# pool_mesurement_circuit.net
KiCad netlist of a schematic drawn in Altium Designer
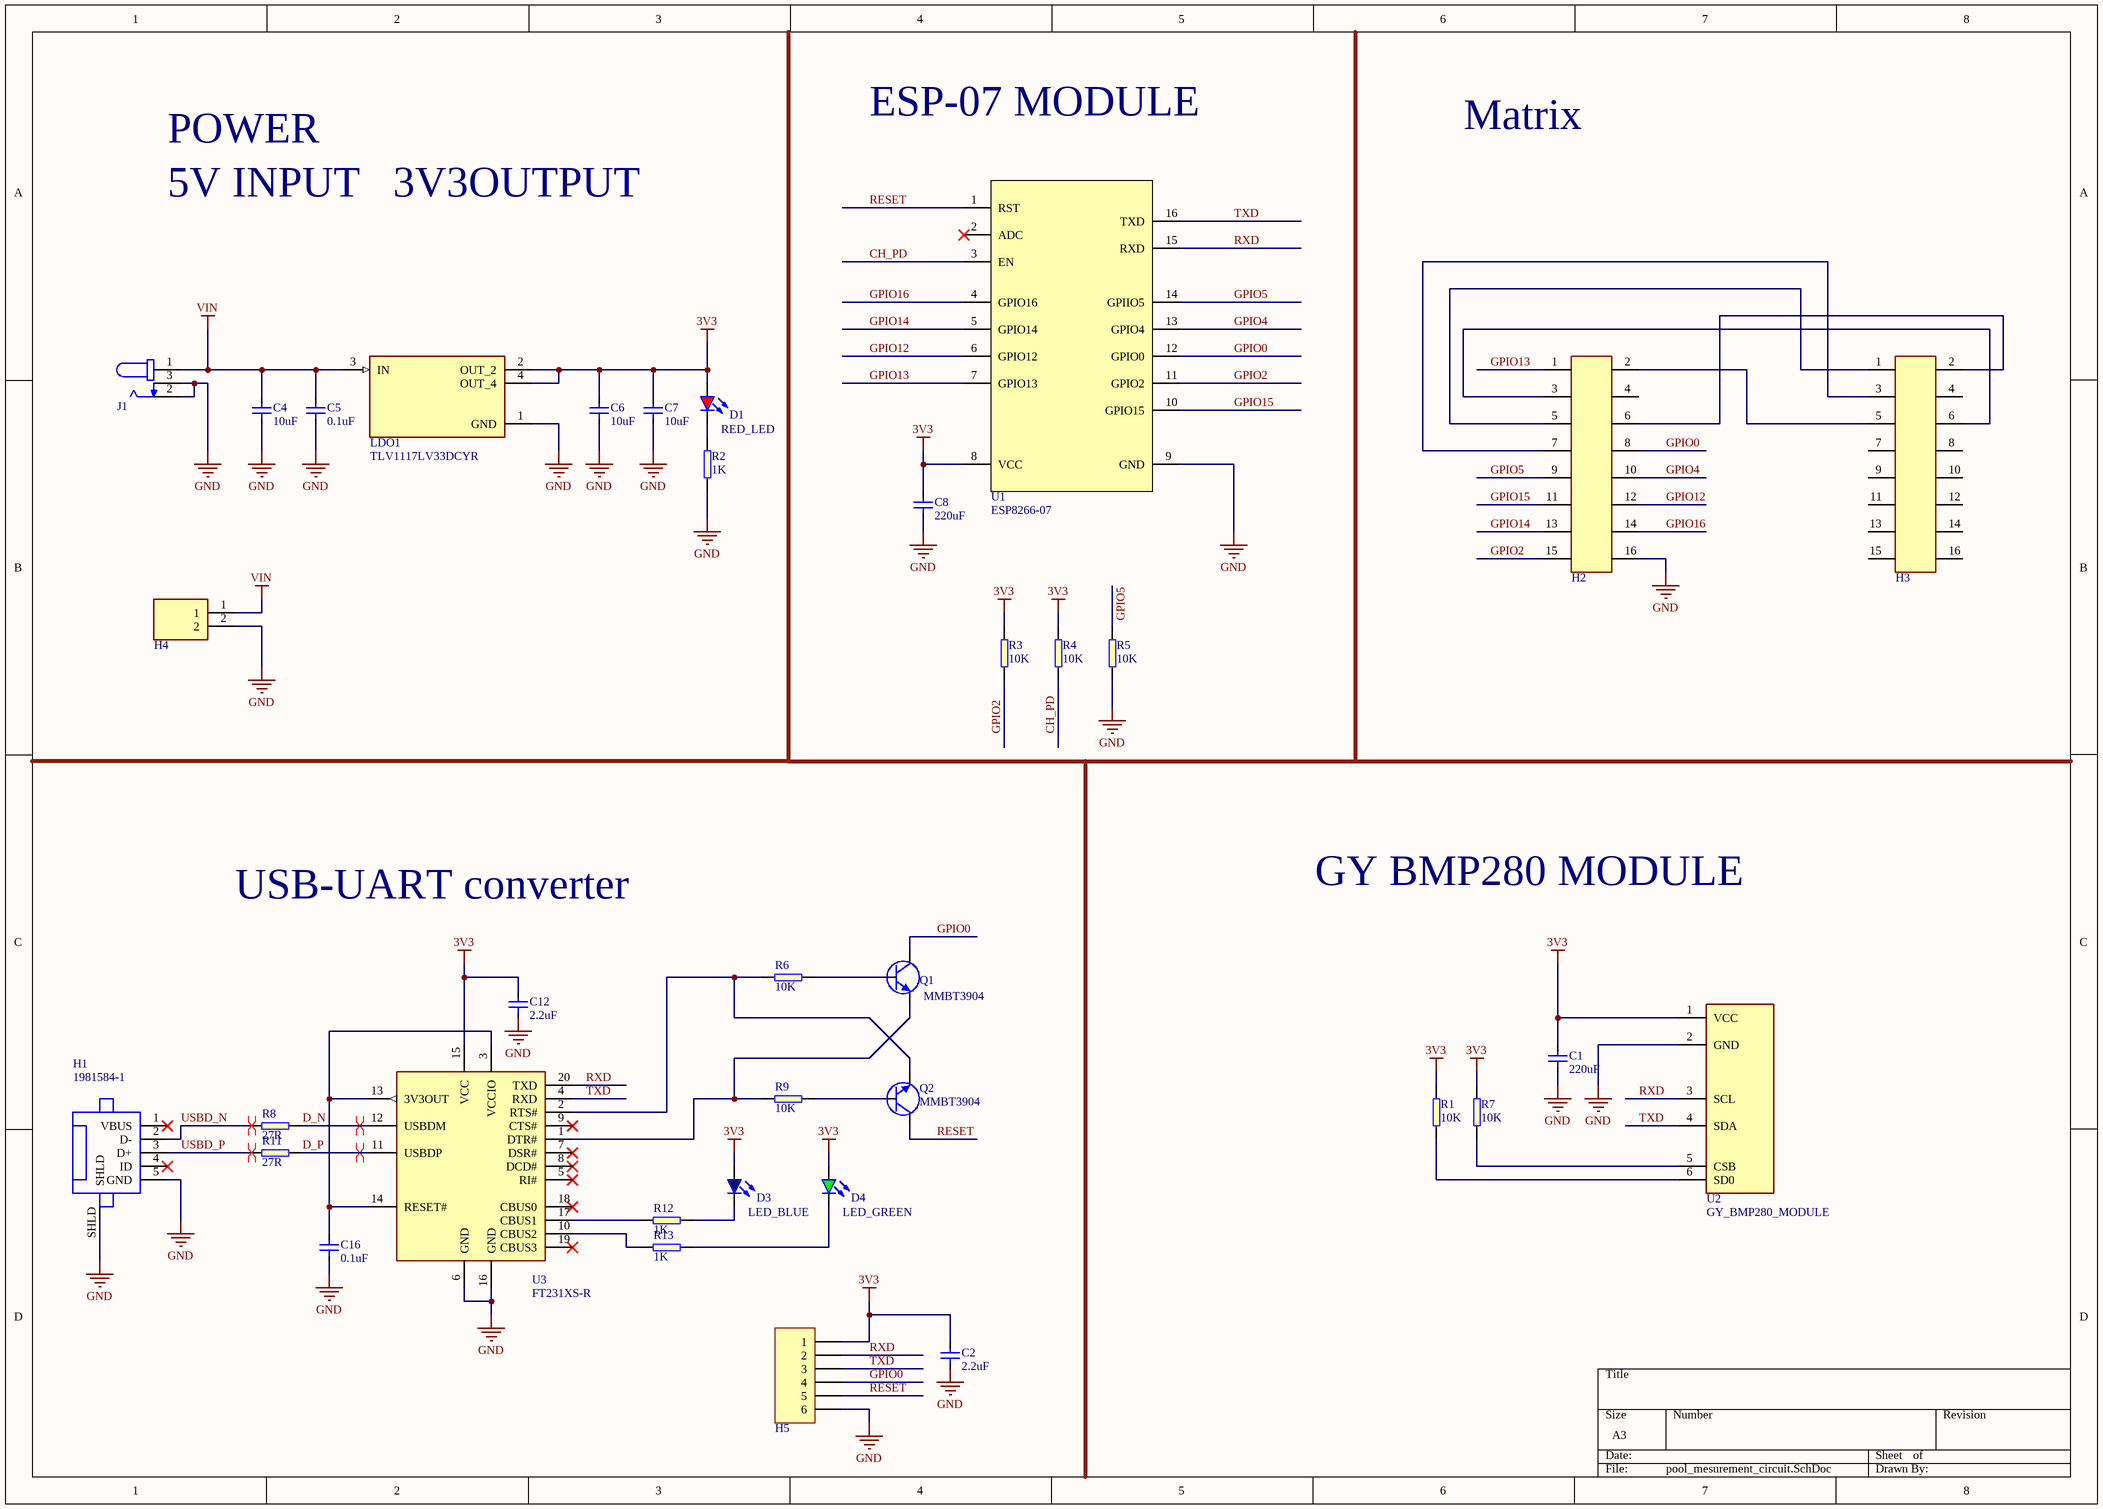
[diagram p0: pool_mesurement_circuit.SchDoc]

(export (version "E")
  (design (tool "Eeschema 10.0.6"))
  (components
    (comp (ref "C1")
      (value "220uF")
      (footprint "C3216")
      (description "SMD capacitor X6S(EIA) with capacitance 220uF Tol.20%. Rated voltage 4Vdc 105C")
      (fields (field (name "MANUFACTURER") "Murata Electronics"))
      (libsource (lib "SchLib") (part "C_220u_3216"))
    )
    (comp (ref "C2")
      (value "2.2uF")
      (footprint "C3216")
      (description "±10% 25V Ceramic Capacitor X7R 1206 (3216 Metric)")
      (fields (field (name "MANUFACTURER") "Samsung Electro-Mechanics"))
      (libsource (lib "SchLib") (part "C_2u2_3216"))
    )
    (comp (ref "C4")
      (value "10uF")
      (footprint "C3216")
      (description "-20%, +80% 10V Ceramic Capacitor Y5V (F) 1206 (3216 Metric)")
      (fields (field (name "MANUFACTURER") "Samsung Electro-Mechanics"))
      (libsource (lib "SchLib") (part "C_10u_3216"))
    )
    (comp (ref "C5")
      (value "0.1uF")
      (footprint "C3216")
      (description "±10% 50V Ceramic Capacitor X7R 1206 (3216 Metric)")
      (fields (field (name "MANUFACTURER") "Samsung Electro-Mechanics"))
      (libsource (lib "SchLib") (part "C_100n_3216"))
    )
    (comp (ref "C6")
      (value "10uF")
      (footprint "C3216")
      (description "-20%, +80% 10V Ceramic Capacitor Y5V (F) 1206 (3216 Metric)")
      (fields (field (name "MANUFACTURER") "Samsung Electro-Mechanics"))
      (libsource (lib "SchLib") (part "C_10u_3216"))
    )
    (comp (ref "C7")
      (value "10uF")
      (footprint "C3216")
      (description "-20%, +80% 10V Ceramic Capacitor Y5V (F) 1206 (3216 Metric)")
      (fields (field (name "MANUFACTURER") "Samsung Electro-Mechanics"))
      (libsource (lib "SchLib") (part "C_10u_3216"))
    )
    (comp (ref "C8")
      (value "220uF")
      (footprint "C3216")
      (description "SMD capacitor X6S(EIA) with capacitance 220uF Tol.20%. Rated voltage 4Vdc 105C")
      (fields (field (name "MANUFACTURER") "Murata Electronics"))
      (libsource (lib "SchLib") (part "C_220u_3216"))
    )
    (comp (ref "C12")
      (value "2.2uF")
      (footprint "C3216")
      (description "±10% 25V Ceramic Capacitor X7R 1206 (3216 Metric)")
      (fields (field (name "MANUFACTURER") "Samsung Electro-Mechanics"))
      (libsource (lib "SchLib") (part "C_2u2_3216"))
    )
    (comp (ref "C16")
      (value "0.1uF")
      (footprint "C3216")
      (description "±10% 50V Ceramic Capacitor X7R 1206 (3216 Metric)")
      (fields (field (name "MANUFACTURER") "Samsung Electro-Mechanics"))
      (libsource (lib "SchLib") (part "C_100n_3216"))
    )
    (comp (ref "D1")
      (value "RED_LED")
      (footprint "LED0603-RED")
      (description "Red 630nm LED Indication - Discrete 1.9V 0603 (1608 Metric)")
      (fields (field (name "MANUFACTURER") "Würth Elektronik"))
      (libsource (lib "SchLib") (part "LED_RED"))
    )
    (comp (ref "D3")
      (value "LED_BLUE")
      (footprint "LED0603-BLUE")
      (description "Blue 470nm LED Indication - Discrete 3.2V 0603 (1608 Metric)")
      (fields (field (name "MANUFACTURER") "Würth Elektronik"))
      (libsource (lib "SchLib") (part "LED_BLUE"))
    )
    (comp (ref "D4")
      (value "LED_GREEN")
      (footprint "LED0603-GRENN")
      (description "Green 520nm LED Indication - Discrete 3.2V 0603 (1608 Metric)")
      (fields (field (name "MANUFACTURER") "Würth Elektronik"))
      (libsource (lib "SchLib") (part "LED_GREEN"))
    )
    (comp (ref "H1")
      (value "1981584-1")
      (footprint "1981584-1")
      (description "Conn Micro USB 2.0 Type AB RCP 5 POS 0.65mm Solder RA SMD 5 Terminal 1 Port T/R")
      (fields (field (name "MANUFACTURER") "TE Connectivity"))
      (libsource (lib "SchLib") (part "1981584-1"))
    )
    (comp (ref "H2")
      (value "PPTC082LFBN-RC")
      (footprint "PPTC082LFBN-RC")
      (description "16 Position Header Connector Through Hole")
      (fields (field (name "MANUFACTURER") "Sullins Connector Solutions"))
      (libsource (lib "SchLib") (part "PPTC082LFBN-RC"))
    )
    (comp (ref "H3")
      (value "302-R161")
      (footprint "302-R161")
      (description "CONN HEADER R/A 16POS 2.54MM")
      (fields (field (name "MANUFACTURER") "On Shore Technology Inc."))
      (libsource (lib "SchLib") (part "302-R161"))
    )
    (comp (ref "H4")
      (value "TB002-500-02BE")
      (footprint "TB002-500-02BE")
      (description "2~24 Poles, Screw Type, Horizontal, 5.0 Pitch, 22~12 _AWG_, Terminal Block Connector")
      (fields (field (name "MANUFACTURER") "CUI Devices"))
      (libsource (lib "SchLib") (part "TB002-500-02BE"))
    )
    (comp (ref "H5")
      (value "PH1-06-UA")
      (footprint "PH1-06-UA")
      (description "Connector Header Through Hole 6 position 0.100\" (2.54mm)")
      (fields (field (name "MANUFACTURER") "Adam Tech"))
      (libsource (lib "SchLib") (part "PH1-06-UA"))
    )
    (comp (ref "J1")
      (value "PJ-002A")
      (footprint "PJ-002A")
      (description "2,0 x 6,5 mm, 2,5 A, Yatay, A莽谋k Delik, Dc G眉莽 Jak谋 Konnekt枚r眉")
      (fields (field (name "MANUFACTURER") "CUI Devices"))
      (libsource (lib "SchLib") (part "PJ-002A"))
    )
    (comp (ref "LDO1")
      (value "TLV1117LV33DCYR")
      (footprint "TLV1117LV33DCYR")
      (description "1-A, low-dropout voltage regulator 4-SOT-223 -40 to 125")
      (fields (field (name "MANUFACTURER") "Texas Instruments"))
      (libsource (lib "SchLib") (part "TLV1117LV33DCYR"))
    )
    (comp (ref "Q1")
      (value "MMBT3904")
      (footprint "MMBT3904")
      (description "Bipolar _BJT_ Transistor NPN 40V 200mA 270MHz 350mW Surface Mount SOT-23-3")
      (fields (field (name "MANUFACTURER") "STMicroelectronics"))
      (libsource (lib "SchLib") (part "MMBT3904"))
    )
    (comp (ref "Q2")
      (value "MMBT3904")
      (footprint "MMBT3904")
      (description "Bipolar _BJT_ Transistor NPN 40V 200mA 270MHz 350mW Surface Mount SOT-23-3")
      (fields (field (name "MANUFACTURER") "STMicroelectronics"))
      (libsource (lib "SchLib") (part "MMBT3904"))
    )
    (comp (ref "R1")
      (value "10K")
      (footprint "R3216")
      (description "10 ±1% 0.25W, 1/4W Chip Resistor 1206 (3216 Metric) Automotive AEC-Q200 Thick Film")
      (fields (field (name "MANUFACTURER") "RMCF1206FT10K0"))
      (libsource (lib "") (part "R_10k_3216_1"))
    )
    (comp (ref "R2")
      (value "1K")
      (footprint "R3216")
      (description "1 ±1% 0.25W, 1/4W Chip Resistor 1206 (3216 Metric) Automotive AEC-Q200 Thick Film")
      (fields (field (name "MANUFACTURER") "Stackpole Electronics Inc"))
      (libsource (lib "SchLib") (part "R_1k_3216"))
    )
    (comp (ref "R3")
      (value "10K")
      (footprint "R3216")
      (description "10 ±1% 0.25W, 1/4W Chip Resistor 1206 (3216 Metric) Automotive AEC-Q200 Thick Film")
      (fields (field (name "MANUFACTURER") "RMCF1206FT10K0"))
      (libsource (lib "") (part "R_10k_3216_1"))
    )
    (comp (ref "R4")
      (value "10K")
      (footprint "R3216")
      (description "10 ±1% 0.25W, 1/4W Chip Resistor 1206 (3216 Metric) Automotive AEC-Q200 Thick Film")
      (fields (field (name "MANUFACTURER") "RMCF1206FT10K0"))
      (libsource (lib "") (part "R_10k_3216_1"))
    )
    (comp (ref "R5")
      (value "10K")
      (footprint "R3216")
      (description "10 ±1% 0.25W, 1/4W Chip Resistor 1206 (3216 Metric) Automotive AEC-Q200 Thick Film")
      (fields (field (name "MANUFACTURER") "RMCF1206FT10K0"))
      (libsource (lib "") (part "R_10k_3216_1"))
    )
    (comp (ref "R6")
      (value "10K")
      (footprint "R3216")
      (description "10 ±1% 0.25W, 1/4W Chip Resistor 1206 (3216 Metric) Automotive AEC-Q200 Thick Film")
      (fields (field (name "MANUFACTURER") "RMCF1206FT10K0"))
      (libsource (lib "SchLib") (part "R_10k_3216"))
    )
    (comp (ref "R7")
      (value "10K")
      (footprint "R3216")
      (description "10 ±1% 0.25W, 1/4W Chip Resistor 1206 (3216 Metric) Automotive AEC-Q200 Thick Film")
      (fields (field (name "MANUFACTURER") "RMCF1206FT10K0"))
      (libsource (lib "") (part "R_10k_3216_1"))
    )
    (comp (ref "R8")
      (value "27R")
      (footprint "R3216")
      (description "27 ±5% 0.25W, 1/4W Chip Resistor 1206 (3216 Metric) Automotive AEC-Q200 Thick Film")
      (fields (field (name "MANUFACTURER") "Stackpole Electronics Inc"))
      (libsource (lib "SchLib") (part "R_27R_3216"))
    )
    (comp (ref "R9")
      (value "10K")
      (footprint "R3216")
      (description "10 ±1% 0.25W, 1/4W Chip Resistor 1206 (3216 Metric) Automotive AEC-Q200 Thick Film")
      (fields (field (name "MANUFACTURER") "RMCF1206FT10K0"))
      (libsource (lib "SchLib") (part "R_10k_3216"))
    )
    (comp (ref "R11")
      (value "27R")
      (footprint "R3216")
      (description "27 ±5% 0.25W, 1/4W Chip Resistor 1206 (3216 Metric) Automotive AEC-Q200 Thick Film")
      (fields (field (name "MANUFACTURER") "Stackpole Electronics Inc"))
      (libsource (lib "SchLib") (part "R_27R_3216"))
    )
    (comp (ref "R12")
      (value "1K")
      (footprint "R3216")
      (description "1 ±1% 0.25W, 1/4W Chip Resistor 1206 (3216 Metric) Automotive AEC-Q200 Thick Film")
      (fields (field (name "MANUFACTURER") "Stackpole Electronics Inc"))
      (libsource (lib "") (part "R_1k_3216_1"))
    )
    (comp (ref "R13")
      (value "1K")
      (footprint "R3216")
      (description "1 ±1% 0.25W, 1/4W Chip Resistor 1206 (3216 Metric) Automotive AEC-Q200 Thick Film")
      (fields (field (name "MANUFACTURER") "Stackpole Electronics Inc"))
      (libsource (lib "") (part "R_1k_3216_1"))
    )
    (comp (ref "U1")
      (value "ESP8266-07")
      (footprint "ESP8266-07_MODULE")
      (description "self-contained Wi-Fi network solution")
      (fields (field (name "MANUFACTURER") "Reland Sung"))
      (libsource (lib "SchLib") (part "ESP8266-07"))
    )
    (comp (ref "U2")
      (value "GY_BMP280_MODULE")
      (footprint "BMP280_MODULE")
      (description "environmental sensor with temperature, barometric pressure")
      (fields (field (name "MANUFACTURER") "KOOBOOK"))
      (libsource (lib "SchLib") (part "GY_BMP280_MODULE"))
    )
    (comp (ref "U3")
      (value "FT231XS-R")
      (footprint "FT231XS-R")
      (description "USB Bridge, USB to UART USB 2.0 UART Interface 20-SSOP")
      (fields (field (name "MANUFACTURER") "FTDI"))
      (libsource (lib "SchLib") (part "FT231XS-R"))
    )
  )
  (nets
    (net (code "1") (name "/CH_PD") (class "Default")
      (node (ref "R4") (pin "1") (pintype "passive"))
      (node (ref "U1") (pin "3") (pinfunction "EN_3") (pintype "passive"))
    )
    (net (code "2") (name "/D_N") (class "Default")
      (node (ref "R8") (pin "2") (pintype "passive"))
      (node (ref "U3") (pin "12") (pinfunction "USBDM_12") (pintype "passive"))
    )
    (net (code "3") (name "/D_P") (class "Default")
      (node (ref "R11") (pin "2") (pintype "passive"))
      (node (ref "U3") (pin "11") (pinfunction "USBDP_11") (pintype "passive"))
    )
    (net (code "4") (name "/GPIO0") (class "Default")
      (node (ref "H2") (pin "8") (pinfunction "8_8") (pintype "passive"))
      (node (ref "H5") (pin "4") (pinfunction "4_4") (pintype "passive"))
      (node (ref "Q1") (pin "3") (pinfunction "C_3") (pintype "passive"))
      (node (ref "U1") (pin "12") (pinfunction "GPIO0_12") (pintype "passive"))
    )
    (net (code "5") (name "/GPIO2") (class "Default")
      (node (ref "H2") (pin "15") (pinfunction "15_15") (pintype "passive"))
      (node (ref "R3") (pin "1") (pintype "passive"))
      (node (ref "U1") (pin "11") (pinfunction "GPIO2_11") (pintype "passive"))
    )
    (net (code "6") (name "/GPIO4") (class "Default")
      (node (ref "H2") (pin "10") (pinfunction "10_10") (pintype "passive"))
      (node (ref "U1") (pin "13") (pinfunction "GPIO4_13") (pintype "passive"))
    )
    (net (code "7") (name "/GPIO5") (class "Default")
      (node (ref "H2") (pin "9") (pinfunction "9_9") (pintype "passive"))
      (node (ref "R5") (pin "2") (pintype "passive"))
      (node (ref "U1") (pin "14") (pinfunction "GPIIO5_14") (pintype "passive"))
    )
    (net (code "8") (name "/GPIO12") (class "Default")
      (node (ref "H2") (pin "12") (pinfunction "12_12") (pintype "passive"))
      (node (ref "U1") (pin "6") (pinfunction "GPIO12_6") (pintype "passive"))
    )
    (net (code "9") (name "/GPIO13") (class "Default")
      (node (ref "H2") (pin "1") (pinfunction "1_1") (pintype "passive"))
      (node (ref "U1") (pin "7") (pinfunction "GPIO13_7") (pintype "passive"))
    )
    (net (code "10") (name "/GPIO14") (class "Default")
      (node (ref "H2") (pin "13") (pinfunction "13_13") (pintype "passive"))
      (node (ref "U1") (pin "5") (pinfunction "GPIO14_5") (pintype "passive"))
    )
    (net (code "11") (name "/GPIO15") (class "Default")
      (node (ref "H2") (pin "11") (pinfunction "11_11") (pintype "passive"))
      (node (ref "U1") (pin "10") (pinfunction "GPIO15_10") (pintype "passive"))
    )
    (net (code "12") (name "/GPIO16") (class "Default")
      (node (ref "H2") (pin "14") (pinfunction "14_14") (pintype "passive"))
      (node (ref "U1") (pin "4") (pinfunction "GPIO16_4") (pintype "passive"))
    )
    (net (code "13") (name "/RESET") (class "Default")
      (node (ref "H5") (pin "5") (pinfunction "5_5") (pintype "passive"))
      (node (ref "Q2") (pin "3") (pinfunction "C_3") (pintype "passive"))
      (node (ref "U1") (pin "1") (pinfunction "RST_1") (pintype "passive"))
    )
    (net (code "14") (name "/RXD") (class "Default")
      (node (ref "H5") (pin "2") (pinfunction "2_2") (pintype "passive"))
      (node (ref "U1") (pin "15") (pinfunction "RXD_15") (pintype "passive"))
      (node (ref "U2") (pin "3") (pinfunction "SCL_3") (pintype "passive"))
      (node (ref "U3") (pin "20") (pinfunction "TXD_20") (pintype "passive"))
    )
    (net (code "15") (name "/TXD") (class "Default")
      (node (ref "H5") (pin "3") (pinfunction "3_3") (pintype "passive"))
      (node (ref "U1") (pin "16") (pinfunction "TXD_16") (pintype "passive"))
      (node (ref "U2") (pin "4") (pinfunction "SDA_4") (pintype "passive"))
      (node (ref "U3") (pin "4") (pinfunction "RXD_4") (pintype "passive"))
    )
    (net (code "16") (name "/USBD_N") (class "Default")
      (node (ref "H1") (pin "2") (pinfunction "D-_2") (pintype "passive"))
      (node (ref "R8") (pin "1") (pintype "passive"))
    )
    (net (code "17") (name "/USBD_P") (class "Default")
      (node (ref "H1") (pin "3") (pinfunction "D+_3") (pintype "passive"))
      (node (ref "R11") (pin "1") (pintype "passive"))
    )
    (net (code "18") (name "3V3") (class "Default")
      (node (ref "C1") (pin "2") (pinfunction "2_2") (pintype "passive"))
      (node (ref "C12") (pin "2") (pinfunction "2_2") (pintype "passive"))
      (node (ref "C2") (pin "2") (pinfunction "2_2") (pintype "passive"))
      (node (ref "C6") (pin "2") (pinfunction "2_2") (pintype "passive"))
      (node (ref "C7") (pin "2") (pinfunction "2_2") (pintype "passive"))
      (node (ref "C8") (pin "2") (pinfunction "2_2") (pintype "passive"))
      (node (ref "D1") (pin "A") (pinfunction "A_A") (pintype "passive"))
      (node (ref "D3") (pin "A") (pinfunction "A_A") (pintype "passive"))
      (node (ref "D4") (pin "A") (pinfunction "A_A") (pintype "passive"))
      (node (ref "H5") (pin "1") (pinfunction "1_1") (pintype "passive"))
      (node (ref "LDO1") (pin "2") (pinfunction "OUT_2_2") (pintype "passive"))
      (node (ref "LDO1") (pin "4") (pinfunction "OUT_4_4") (pintype "passive"))
      (node (ref "R1") (pin "2") (pintype "passive"))
      (node (ref "R3") (pin "2") (pintype "passive"))
      (node (ref "R4") (pin "2") (pintype "passive"))
      (node (ref "R7") (pin "2") (pintype "passive"))
      (node (ref "U1") (pin "8") (pinfunction "VCC_8") (pintype "passive"))
      (node (ref "U2") (pin "1") (pinfunction "VCC_1") (pintype "passive"))
      (node (ref "U3") (pin "15") (pinfunction "VCC_15") (pintype "passive"))
    )
    (net (code "19") (name "GND") (class "Default")
      (node (ref "C1") (pin "1") (pinfunction "1_1") (pintype "passive"))
      (node (ref "C12") (pin "1") (pinfunction "1_1") (pintype "passive"))
      (node (ref "C16") (pin "1") (pinfunction "1_1") (pintype "passive"))
      (node (ref "C2") (pin "1") (pinfunction "1_1") (pintype "passive"))
      (node (ref "C4") (pin "1") (pinfunction "1_1") (pintype "passive"))
      (node (ref "C5") (pin "1") (pinfunction "1_1") (pintype "passive"))
      (node (ref "C6") (pin "1") (pinfunction "1_1") (pintype "passive"))
      (node (ref "C7") (pin "1") (pinfunction "1_1") (pintype "passive"))
      (node (ref "C8") (pin "1") (pinfunction "1_1") (pintype "passive"))
      (node (ref "H1") (pin "5") (pinfunction "GND_5") (pintype "passive"))
      (node (ref "H1") (pin "SHLD") (pinfunction "SHLD_SHLD") (pintype "passive"))
      (node (ref "H2") (pin "16") (pinfunction "16_16") (pintype "passive"))
      (node (ref "H4") (pin "2") (pinfunction "2_2") (pintype "passive"))
      (node (ref "H5") (pin "6") (pinfunction "6_6") (pintype "passive"))
      (node (ref "J1") (pin "2") (pinfunction "2_2") (pintype "passive"))
      (node (ref "J1") (pin "3") (pinfunction "3_3") (pintype "passive"))
      (node (ref "LDO1") (pin "1") (pinfunction "GND_1") (pintype "power_in"))
      (node (ref "R2") (pin "1") (pintype "passive"))
      (node (ref "R5") (pin "1") (pintype "passive"))
      (node (ref "U1") (pin "9") (pinfunction "GND_9") (pintype "passive"))
      (node (ref "U2") (pin "2") (pinfunction "GND_2") (pintype "passive"))
      (node (ref "U3") (pin "16") (pinfunction "GND_16") (pintype "passive"))
      (node (ref "U3") (pin "6") (pinfunction "GND_6") (pintype "passive"))
    )
    (net (code "20") (name "Net-(D1-PadK)") (class "Default")
      (node (ref "D1") (pin "K") (pinfunction "K_K") (pintype "passive"))
      (node (ref "R2") (pin "2") (pintype "passive"))
    )
    (net (code "21") (name "Net-(D3-PadK)") (class "Default")
      (node (ref "D3") (pin "K") (pinfunction "K_K") (pintype "passive"))
      (node (ref "R12") (pin "1") (pintype "passive"))
    )
    (net (code "22") (name "Net-(D4-PadK)") (class "Default")
      (node (ref "D4") (pin "K") (pinfunction "K_K") (pintype "passive"))
      (node (ref "R13") (pin "1") (pintype "passive"))
    )
    (net (code "23") (name "Net-(H2-Pad2)") (class "Default")
      (node (ref "H2") (pin "2") (pinfunction "2_2") (pintype "passive"))
      (node (ref "H3") (pin "5") (pinfunction "5_5") (pintype "passive"))
    )
    (net (code "24") (name "Net-(H2-Pad3)") (class "Default")
      (node (ref "H2") (pin "3") (pinfunction "3_3") (pintype "passive"))
      (node (ref "H3") (pin "6") (pinfunction "6_6") (pintype "passive"))
    )
    (net (code "25") (name "Net-(H2-Pad5)") (class "Default")
      (node (ref "H2") (pin "5") (pinfunction "5_5") (pintype "passive"))
      (node (ref "H3") (pin "1") (pinfunction "1_1") (pintype "passive"))
    )
    (net (code "26") (name "Net-(H2-Pad6)") (class "Default")
      (node (ref "H2") (pin "6") (pinfunction "6_6") (pintype "passive"))
      (node (ref "H3") (pin "2") (pinfunction "2_2") (pintype "passive"))
    )
    (net (code "27") (name "Net-(H2-Pad7)") (class "Default")
      (node (ref "H2") (pin "7") (pinfunction "7_7") (pintype "passive"))
      (node (ref "H3") (pin "3") (pinfunction "3_3") (pintype "passive"))
    )
    (net (code "28") (name "Net-(Q1-B)") (class "Default")
      (node (ref "Q1") (pin "1") (pinfunction "B_1") (pintype "passive"))
      (node (ref "R6") (pin "1") (pintype "passive"))
    )
    (net (code "29") (name "Net-(Q1-E)") (class "Default")
      (node (ref "Q1") (pin "2") (pinfunction "E_2") (pintype "passive"))
      (node (ref "R9") (pin "2") (pintype "passive"))
      (node (ref "U3") (pin "1") (pinfunction "DTR#_1") (pintype "passive"))
    )
    (net (code "30") (name "Net-(Q2-B)") (class "Default")
      (node (ref "Q2") (pin "1") (pinfunction "B_1") (pintype "passive"))
      (node (ref "R9") (pin "1") (pintype "passive"))
    )
    (net (code "31") (name "Net-(Q2-E)") (class "Default")
      (node (ref "Q2") (pin "2") (pinfunction "E_2") (pintype "passive"))
      (node (ref "R6") (pin "2") (pintype "passive"))
      (node (ref "U3") (pin "2") (pinfunction "RTS#_2") (pintype "passive"))
    )
    (net (code "32") (name "Net-(U2-CSB)") (class "Default")
      (node (ref "R7") (pin "1") (pintype "passive"))
      (node (ref "U2") (pin "5") (pinfunction "CSB_5") (pintype "passive"))
    )
    (net (code "33") (name "Net-(U2-SD0)") (class "Default")
      (node (ref "R1") (pin "1") (pintype "passive"))
      (node (ref "U2") (pin "6") (pinfunction "SD0_6") (pintype "passive"))
    )
    (net (code "34") (name "Net-(U3-3V3OUT)") (class "Default")
      (node (ref "C16") (pin "2") (pinfunction "2_2") (pintype "passive"))
      (node (ref "U3") (pin "13") (pinfunction "3V3OUT_13") (pintype "output"))
      (node (ref "U3") (pin "14") (pinfunction "RESET#_14") (pintype "passive"))
      (node (ref "U3") (pin "3") (pinfunction "VCCIO_3") (pintype "passive"))
    )
    (net (code "35") (name "Net-(U3-CBUS1)") (class "Default")
      (node (ref "R12") (pin "2") (pintype "passive"))
      (node (ref "U3") (pin "17") (pinfunction "CBUS1_17") (pintype "passive"))
    )
    (net (code "36") (name "Net-(U3-CBUS2)") (class "Default")
      (node (ref "R13") (pin "2") (pintype "passive"))
      (node (ref "U3") (pin "10") (pinfunction "CBUS2_10") (pintype "passive"))
    )
    (net (code "37") (name "VIN") (class "Default")
      (node (ref "C4") (pin "2") (pinfunction "2_2") (pintype "passive"))
      (node (ref "C5") (pin "2") (pinfunction "2_2") (pintype "passive"))
      (node (ref "H4") (pin "1") (pinfunction "1_1") (pintype "passive"))
      (node (ref "J1") (pin "1") (pinfunction "1_1") (pintype "passive"))
      (node (ref "LDO1") (pin "3") (pinfunction "IN_3") (pintype "input"))
    )
    (net (code "38") (name "unconnected-(H1-ID-Pad4)") (class "Default")
      (node (ref "H1") (pin "4") (pinfunction "ID_4") (pintype "passive+no_connect"))
    )
    (net (code "39") (name "unconnected-(H1-VBUS-Pad1)") (class "Default")
      (node (ref "H1") (pin "1") (pinfunction "VBUS_1") (pintype "passive+no_connect"))
    )
    (net (code "40") (name "unconnected-(H2-Pad4)") (class "Default")
      (node (ref "H2") (pin "4") (pinfunction "4_4") (pintype "passive"))
    )
    (net (code "41") (name "unconnected-(H3-Pad4)") (class "Default")
      (node (ref "H3") (pin "4") (pinfunction "4_4") (pintype "passive"))
    )
    (net (code "42") (name "unconnected-(H3-Pad7)") (class "Default")
      (node (ref "H3") (pin "7") (pinfunction "7_7") (pintype "passive"))
    )
    (net (code "43") (name "unconnected-(H3-Pad8)") (class "Default")
      (node (ref "H3") (pin "8") (pinfunction "8_8") (pintype "passive"))
    )
    (net (code "44") (name "unconnected-(H3-Pad9)") (class "Default")
      (node (ref "H3") (pin "9") (pinfunction "9_9") (pintype "passive"))
    )
    (net (code "45") (name "unconnected-(H3-Pad10)") (class "Default")
      (node (ref "H3") (pin "10") (pinfunction "10_10") (pintype "passive"))
    )
    (net (code "46") (name "unconnected-(H3-Pad11)") (class "Default")
      (node (ref "H3") (pin "11") (pinfunction "11_11") (pintype "passive"))
    )
    (net (code "47") (name "unconnected-(H3-Pad12)") (class "Default")
      (node (ref "H3") (pin "12") (pinfunction "12_12") (pintype "passive"))
    )
    (net (code "48") (name "unconnected-(H3-Pad13)") (class "Default")
      (node (ref "H3") (pin "13") (pinfunction "13_13") (pintype "passive"))
    )
    (net (code "49") (name "unconnected-(H3-Pad14)") (class "Default")
      (node (ref "H3") (pin "14") (pinfunction "14_14") (pintype "passive"))
    )
    (net (code "50") (name "unconnected-(H3-Pad15)") (class "Default")
      (node (ref "H3") (pin "15") (pinfunction "15_15") (pintype "passive"))
    )
    (net (code "51") (name "unconnected-(H3-Pad16)") (class "Default")
      (node (ref "H3") (pin "16") (pinfunction "16_16") (pintype "passive"))
    )
    (net (code "52") (name "unconnected-(U1-ADC-Pad2)") (class "Default")
      (node (ref "U1") (pin "2") (pinfunction "ADC_2") (pintype "passive+no_connect"))
    )
    (net (code "53") (name "unconnected-(U3-CBUS0-Pad18)") (class "Default")
      (node (ref "U3") (pin "18") (pinfunction "CBUS0_18") (pintype "passive+no_connect"))
    )
    (net (code "54") (name "unconnected-(U3-CBUS3-Pad19)") (class "Default")
      (node (ref "U3") (pin "19") (pinfunction "CBUS3_19") (pintype "passive+no_connect"))
    )
    (net (code "55") (name "unconnected-(U3-CTS#-Pad9)") (class "Default")
      (node (ref "U3") (pin "9") (pinfunction "CTS#_9") (pintype "passive+no_connect"))
    )
    (net (code "56") (name "unconnected-(U3-DCD#-Pad8)") (class "Default")
      (node (ref "U3") (pin "8") (pinfunction "DCD#_8") (pintype "passive+no_connect"))
    )
    (net (code "57") (name "unconnected-(U3-DSR#-Pad7)") (class "Default")
      (node (ref "U3") (pin "7") (pinfunction "DSR#_7") (pintype "passive+no_connect"))
    )
    (net (code "58") (name "unconnected-(U3-RI#-Pad5)") (class "Default")
      (node (ref "U3") (pin "5") (pinfunction "RI#_5") (pintype "passive+no_connect"))
    )
  )
)
